# SparkFun_GNSS_NEO-M9N.net
KiCad netlist of a schematic drawn in EAGLE
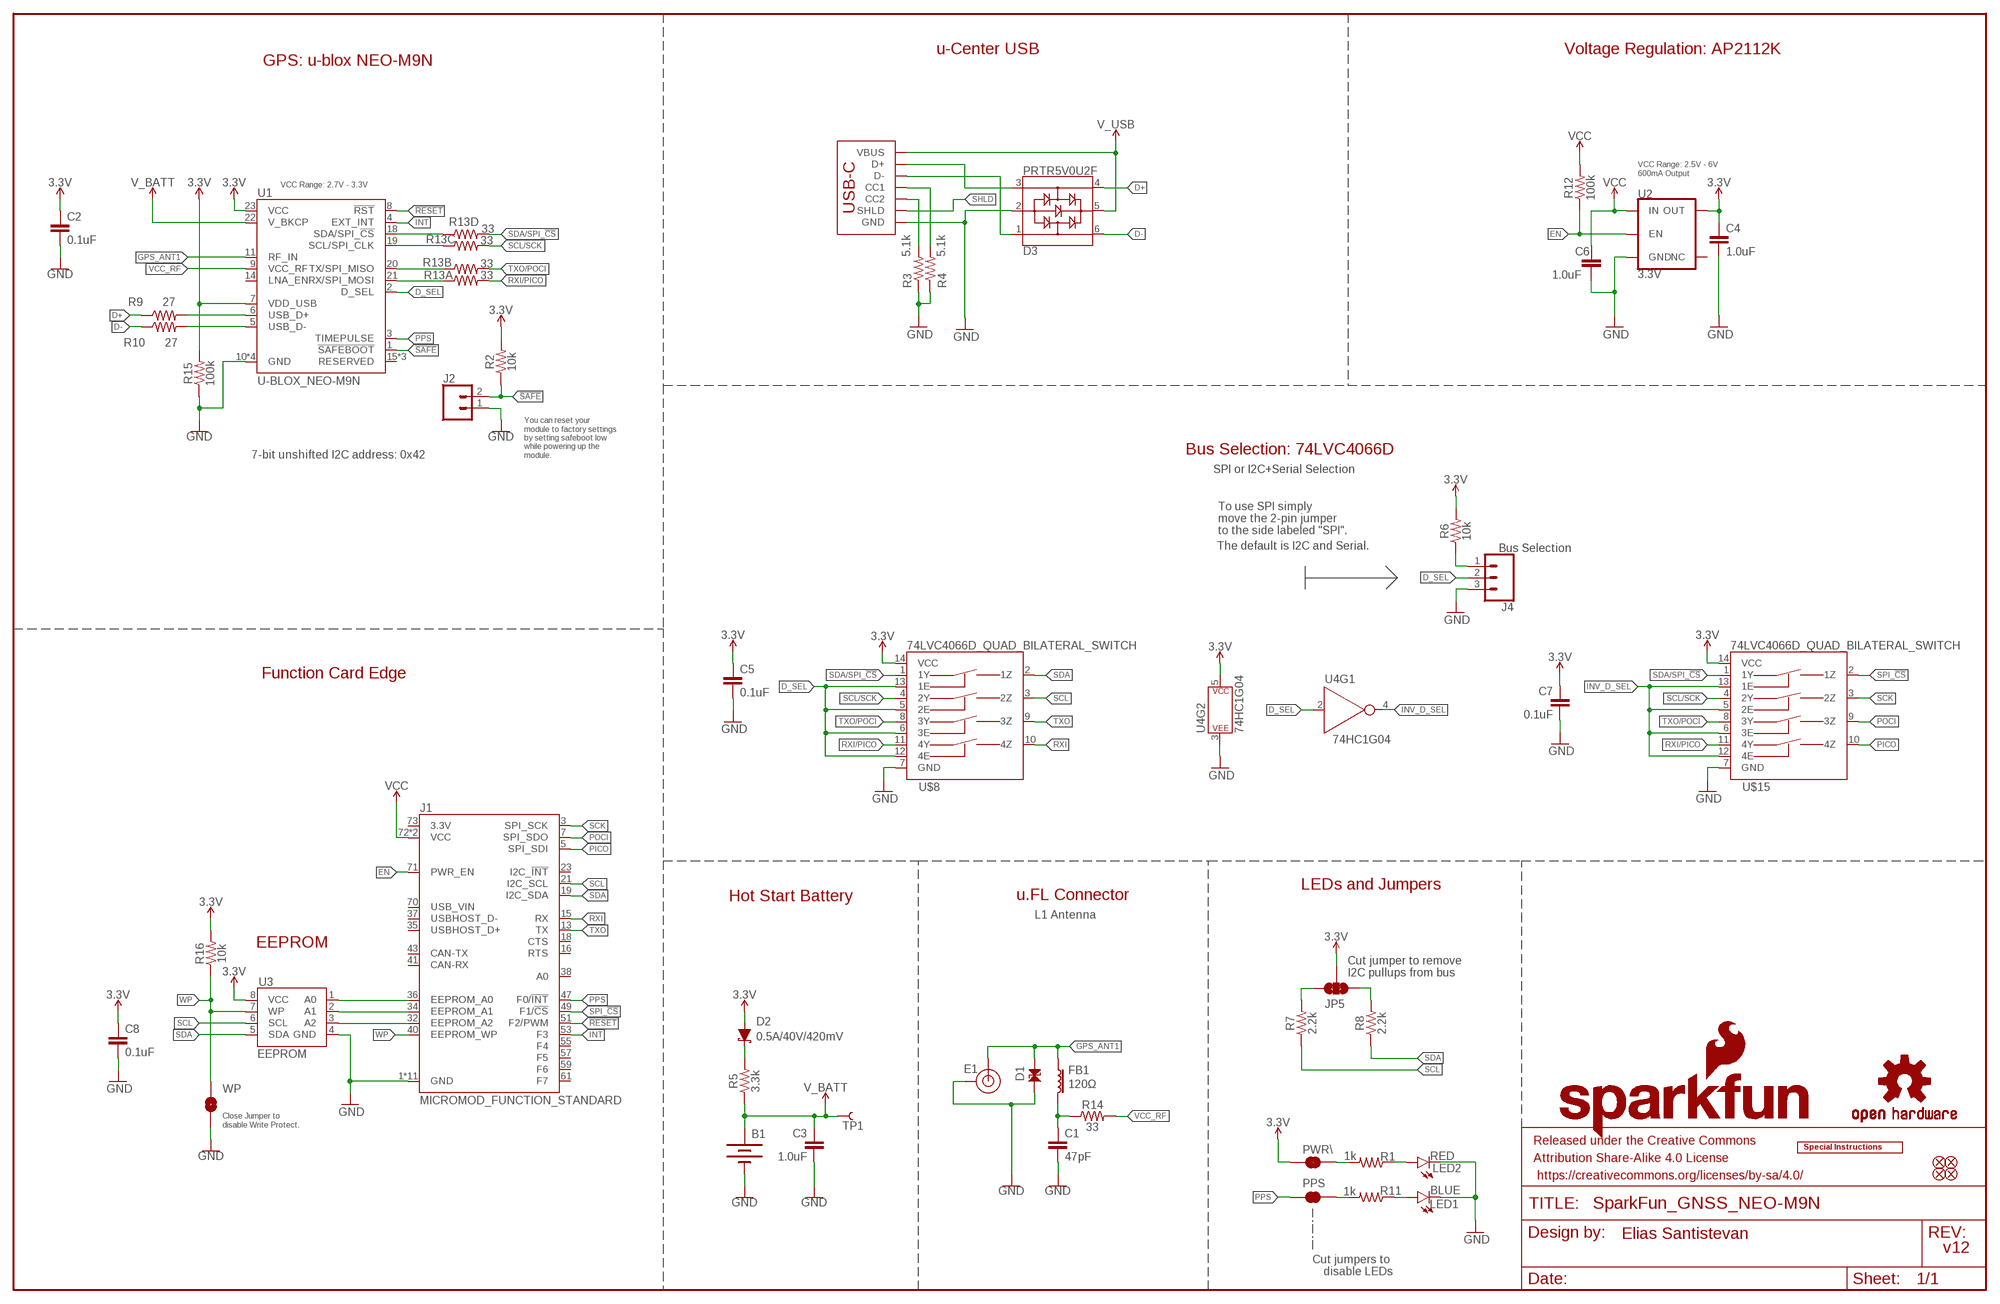
[diagram p0: schematic, sheet 1]

(export (version "E")
  (design (tool "Eeschema 10.0.6"))
  (components
    (comp (ref "B1")
      (value "6.8MM_COIN_CELL")
      (footprint "eagle-import:MS421R_IV03E")
      (libsource (lib "eagle-import") (part "RELOWABLE_BATTERY_MS421R"))
    )
    (comp (ref "C1")
      (value "47pF")
      (footprint "eagle-import:0402")
      (libsource (lib "eagle-import") (part "47PF-0402-25V-5%-X7R"))
    )
    (comp (ref "C2")
      (value "0.1uF")
      (footprint "eagle-import:0402-TIGHT")
      (libsource (lib "eagle-import") (part "0.1UF-0402T-16V-10%"))
    )
    (comp (ref "C3")
      (value "1.0uF")
      (footprint "eagle-import:0603")
      (libsource (lib "eagle-import") (part "1.0UF-0603-16V-10%"))
    )
    (comp (ref "C4")
      (value "1.0uF")
      (footprint "eagle-import:0603")
      (libsource (lib "eagle-import") (part "1.0UF-0603-16V-10%"))
    )
    (comp (ref "C5")
      (value "0.1uF")
      (footprint "eagle-import:0603")
      (libsource (lib "eagle-import") (part "0.1UF-0603-25V-(+80/-20%)"))
    )
    (comp (ref "C6")
      (value "1.0uF")
      (footprint "eagle-import:0603")
      (libsource (lib "eagle-import") (part "1.0UF-0603-16V-10%"))
    )
    (comp (ref "C7")
      (value "0.1uF")
      (footprint "eagle-import:0603")
      (libsource (lib "eagle-import") (part "0.1UF-0603-25V-(+80/-20%)"))
    )
    (comp (ref "C8")
      (value "0.1uF")
      (footprint "eagle-import:0603")
      (libsource (lib "eagle-import") (part "0.1UF-0603-25V-(+80/-20%)"))
    )
    (comp (ref "D1")
      (value "PESD0402-0402T")
      (footprint "eagle-import:0402-TIGHT")
      (libsource (lib "eagle-import") (part "PESD0402-0402T"))
    )
    (comp (ref "D2")
      (value "0.5A/40V/420mV")
      (footprint "eagle-import:SOD-323")
      (libsource (lib "eagle-import") (part "DIODE-SCHOTTKY-PMEG4005EJ"))
    )
    (comp (ref "D3")
      (value "PRTR5V0U2F")
      (footprint "eagle-import:SOT886")
      (libsource (lib "eagle-import") (part "PRTR5V0U2F"))
    )
    (comp (ref "E1")
      (value "U.FL")
      (footprint "eagle-import:U.FL")
      (libsource (lib "eagle-import") (part "U.FL2PIN"))
    )
    (comp (ref "FB1")
      (value "120Ω")
      (footprint "eagle-import:0402")
      (fields (field (name "MFG_PART") "BLM15HB121SN1D"))
      (libsource (lib "eagle-import") (part "FERRITE_BEAD-120_OHM-0402"))
    )
    (comp (ref "FD1")
      (value "FIDUCIAL1X2")
      (footprint "eagle-import:FIDUCIAL-1X2")
      (libsource (lib "eagle-import") (part "FIDUCIAL1X2"))
    )
    (comp (ref "FD2")
      (value "FIDUCIAL1X2")
      (footprint "eagle-import:FIDUCIAL-1X2")
      (libsource (lib "eagle-import") (part "FIDUCIAL1X2"))
    )
    (comp (ref "FD3")
      (value "FIDUCIAL1X2")
      (footprint "eagle-import:FIDUCIAL-1X2")
      (libsource (lib "eagle-import") (part "FIDUCIAL1X2"))
    )
    (comp (ref "FD4")
      (value "FIDUCIAL1X2")
      (footprint "eagle-import:FIDUCIAL-1X2")
      (libsource (lib "eagle-import") (part "FIDUCIAL1X2"))
    )
    (comp (ref "FRAME2")
      (value "FRAME-LEDGER")
      (footprint "eagle-import:CREATIVE_COMMONS")
      (libsource (lib "eagle-import") (part "FRAME-LEDGER"))
    )
    (comp (ref "J1")
      (value "MICROMOD_FUNCTION_STANDARD")
      (footprint "eagle-import:M.2-CARD-E-22_FUNCTION_STANDARD")
      (libsource (lib "eagle-import") (part "MICROMOD_FUNCTION_STANDARD"))
    )
    (comp (ref "J2")
      (value "CONN_02")
      (footprint "eagle-import:1X02")
      (libsource (lib "eagle-import") (part "CONN_02"))
    )
    (comp (ref "J3")
      (value "USB_C_2-LAYER_PADS")
      (footprint "eagle-import:USB-C-16P-2LAYER-PADS")
      (libsource (lib "eagle-import") (part "USB_C_2-LAYER_PADS"))
    )
    (comp (ref "J4")
      (value "Bus Selection")
      (footprint "eagle-import:1X03_LOCK")
      (libsource (lib "eagle-import") (part "CONN_03LOCK"))
    )
    (comp (ref "JP5")
      (value "JUMPER-SMT_3_2-NC_TRACE_SILK")
      (footprint "eagle-import:SMT-JUMPER_3_2-NC_TRACE_SILK")
      (libsource (lib "eagle-import") (part "JUMPER-SMT_3_2-NC_TRACE_SILK"))
    )
    (comp (ref "LED1")
      (value "BLUE")
      (footprint "eagle-import:LED-0603")
      (libsource (lib "eagle-import") (part "LED-BLUE0603"))
    )
    (comp (ref "LED2")
      (value "RED")
      (footprint "eagle-import:LED-0603")
      (libsource (lib "eagle-import") (part "LED-RED0603"))
    )
    (comp (ref "LOGO1")
      (value "SPECIAL_INSTRUCTIONS-ORDERING")
      (footprint "eagle-import:ORDERING_INSTRUCTIONS")
      (libsource (lib "eagle-import") (part "SPECIAL_INSTRUCTIONS-ORDERING"))
    )
    (comp (ref "LOGO2")
      (value "SFE_LOGO_NAME_FLAME.2_INCH")
      (footprint "eagle-import:SFE_LOGO_NAME_FLAME_.2")
      (libsource (lib "eagle-import") (part "SFE_LOGO_NAME_FLAME.2_INCH"))
    )
    (comp (ref "LOGO3")
      (value "OSHW-LOGOS")
      (footprint "eagle-import:OSHW-LOGO-S")
      (libsource (lib "eagle-import") (part "OSHW-LOGOS"))
    )
    (comp (ref "PPS")
      (value "JUMPER-SMT_2_NC_TRACE_SILK")
      (footprint "eagle-import:SMT-JUMPER_2_NC_TRACE_SILK")
      (libsource (lib "eagle-import") (part "JUMPER-SMT_2_NC_TRACE_SILK"))
    )
    (comp (ref "PWR\\")
      (value "JUMPER-SMT_2_NC_TRACE_SILK")
      (footprint "eagle-import:SMT-JUMPER_2_NC_TRACE_SILK")
      (libsource (lib "eagle-import") (part "JUMPER-SMT_2_NC_TRACE_SILK"))
    )
    (comp (ref "R1")
      (value "1k")
      (footprint "eagle-import:0603")
      (libsource (lib "eagle-import") (part "1KOHM-0603-1/10W-1%"))
    )
    (comp (ref "R2")
      (value "10k")
      (footprint "eagle-import:0603")
      (libsource (lib "eagle-import") (part "10KOHM-0603-1/10W-1%"))
    )
    (comp (ref "R3")
      (value "5.1k")
      (footprint "eagle-import:0603")
      (libsource (lib "eagle-import") (part "5.1KOHM5.1KOHM-0603-1/10W-1%"))
    )
    (comp (ref "R4")
      (value "5.1k")
      (footprint "eagle-import:0603")
      (libsource (lib "eagle-import") (part "5.1KOHM5.1KOHM-0603-1/10W-1%"))
    )
    (comp (ref "R5")
      (value "3.3k")
      (footprint "eagle-import:0603")
      (libsource (lib "eagle-import") (part "3.3KOHM-0603-1/10W-1%"))
    )
    (comp (ref "R6")
      (value "10k")
      (footprint "eagle-import:0603")
      (libsource (lib "eagle-import") (part "10KOHM-0603-1/10W-1%"))
    )
    (comp (ref "R7")
      (value "2.2k")
      (footprint "eagle-import:0603")
      (libsource (lib "eagle-import") (part "2.2KOHM-0603-1/10W-1%"))
    )
    (comp (ref "R8")
      (value "2.2k")
      (footprint "eagle-import:0603")
      (libsource (lib "eagle-import") (part "2.2KOHM-0603-1/10W-1%"))
    )
    (comp (ref "R9")
      (value "27")
      (footprint "eagle-import:0603")
      (libsource (lib "eagle-import") (part "27OHM-0603-1/10W-1%"))
    )
    (comp (ref "R10")
      (value "27")
      (footprint "eagle-import:0603")
      (libsource (lib "eagle-import") (part "27OHM-0603-1/10W-1%"))
    )
    (comp (ref "R11")
      (value "1k")
      (footprint "eagle-import:0603")
      (libsource (lib "eagle-import") (part "1KOHM-0603-1/10W-1%"))
    )
    (comp (ref "R12")
      (value "100k")
      (footprint "eagle-import:0603")
      (libsource (lib "eagle-import") (part "100KOHM-0603-1/10W-1%"))
    )
    (comp (ref "R13")
      (value "33")
      (footprint "eagle-import:1206_RA")
      (libsource (lib "eagle-import") (part "33OHM_RA-1206-1/16W-5%"))
    )
    (comp (ref "R14")
      (value "33")
      (footprint "eagle-import:0402")
      (libsource (lib "eagle-import") (part "33OHM-0402-1/10W-1%"))
    )
    (comp (ref "R15")
      (value "100k")
      (footprint "eagle-import:0603")
      (libsource (lib "eagle-import") (part "100KOHM-0603-1/10W-1%"))
    )
    (comp (ref "R16")
      (value "10k")
      (footprint "eagle-import:0603")
      (libsource (lib "eagle-import") (part "10KOHM-0603-1/10W-1%"))
    )
    (comp (ref "TP1")
      (value "TEST-POINT3X4")
      (footprint "eagle-import:PAD.03X.04")
      (libsource (lib "eagle-import") (part "TEST-POINT3X4"))
    )
    (comp (ref "U$8")
      (value "74LVC4066D_QUAD_BILATERAL_SWITCH")
      (footprint "eagle-import:SO14")
      (libsource (lib "eagle-import") (part "74LVC4066D_QUAD_BILATERAL_SWITCH"))
    )
    (comp (ref "U$15")
      (value "74LVC4066D_QUAD_BILATERAL_SWITCH")
      (footprint "eagle-import:SO14")
      (libsource (lib "eagle-import") (part "74LVC4066D_QUAD_BILATERAL_SWITCH"))
    )
    (comp (ref "U1")
      (value "U-BLOX_NEO-M9N")
      (footprint "eagle-import:NEO-M9N_M8T_M8U_D9S")
      (libsource (lib "eagle-import") (part "U-BLOX_NEO-M9N"))
    )
    (comp (ref "U2")
      (value "3.3V")
      (footprint "eagle-import:SOT23-5")
      (libsource (lib "eagle-import") (part "V_REG_AP2112K-3.3V"))
    )
    (comp (ref "U3")
      (value "EEPROM")
      (footprint "eagle-import:SO08")
      (libsource (lib "eagle-import") (part "EEPROM-I2C512K"))
    )
    (comp (ref "U4")
      (value "74HC1G04")
      (footprint "eagle-import:SOT353")
      (libsource (lib "eagle-import") (part "741G04HC"))
    )
    (comp (ref "WP")
      (value "JUMPER-SMT_2_NO_SILK")
      (footprint "eagle-import:SMT-JUMPER_2_NO_SILK")
      (libsource (lib "eagle-import") (part "JUMPER-SMT_2_NO_SILK"))
    )
  )
  (nets
    (net (code "1") (name "/SDA{slash}SPI_~{CS}") (class "Default")
      (node (ref "R13") (pin "P5") (pinfunction "2_P5") (pintype "passive"))
      (node (ref "U$15") (pin "1") (pinfunction "1Y_1") (pintype "bidirectional"))
      (node (ref "U$8") (pin "1") (pinfunction "1Y_1") (pintype "bidirectional"))
    )
    (net (code "2") (name "/SPI_~{CS}") (class "Default")
      (node (ref "J1") (pin "49") (pinfunction "F1/~{CS}_49") (pintype "bidirectional"))
      (node (ref "U$15") (pin "2") (pinfunction "1Z_2") (pintype "bidirectional"))
    )
    (net (code "3") (name "/~{RESET}") (class "Default")
      (node (ref "J1") (pin "51") (pinfunction "F2/PWM_51") (pintype "bidirectional"))
      (node (ref "U1") (pin "8") (pinfunction "~{RST}_8") (pintype "bidirectional"))
    )
    (net (code "4") (name "/~{SAFE}") (class "Default")
      (node (ref "J2") (pin "2") (pinfunction "2_2") (pintype "passive"))
      (node (ref "R2") (pin "1") (pinfunction "1_1") (pintype "passive"))
      (node (ref "U1") (pin "1") (pinfunction "~{SAFEBOOT}_1") (pintype "bidirectional"))
    )
    (net (code "5") (name "3.3V") (class "Default")
      (node (ref "C2") (pin "1") (pinfunction "1_1") (pintype "passive"))
      (node (ref "C4") (pin "1") (pinfunction "1_1") (pintype "passive"))
      (node (ref "C5") (pin "1") (pinfunction "1_1") (pintype "passive"))
      (node (ref "C7") (pin "1") (pinfunction "1_1") (pintype "passive"))
      (node (ref "C8") (pin "1") (pinfunction "1_1") (pintype "passive"))
      (node (ref "D2") (pin "A") (pinfunction "A_A") (pintype "passive"))
      (node (ref "JP5") (pin "2") (pinfunction "2_2") (pintype "passive"))
      (node (ref "PWR\\") (pin "2") (pinfunction "2_2") (pintype "passive"))
      (node (ref "R15") (pin "2") (pinfunction "2_2") (pintype "passive"))
      (node (ref "R16") (pin "2") (pinfunction "2_2") (pintype "passive"))
      (node (ref "R2") (pin "2") (pinfunction "2_2") (pintype "passive"))
      (node (ref "R6") (pin "2") (pinfunction "2_2") (pintype "passive"))
      (node (ref "U$15") (pin "14") (pinfunction "VCC_14") (pintype "bidirectional"))
      (node (ref "U$8") (pin "14") (pinfunction "VCC_14") (pintype "bidirectional"))
      (node (ref "U1") (pin "23") (pinfunction "VCC_23") (pintype "bidirectional"))
      (node (ref "U1") (pin "7") (pinfunction "VDD_USB_7") (pintype "bidirectional"))
      (node (ref "U2") (pin "5") (pinfunction "OUT_5") (pintype "passive"))
      (node (ref "U3") (pin "8") (pinfunction "VCC_8") (pintype "power_in"))
      (node (ref "U4") (pin "5") (pinfunction "P$V+_5") (pintype "bidirectional"))
    )
    (net (code "6") (name "D+") (class "Default")
      (node (ref "D3") (pin "4") (pinfunction "4_4") (pintype "bidirectional"))
      (node (ref "R9") (pin "1") (pinfunction "1_1") (pintype "passive"))
    )
    (net (code "7") (name "D-") (class "Default")
      (node (ref "D3") (pin "6") (pinfunction "6_6") (pintype "bidirectional"))
      (node (ref "R10") (pin "1") (pinfunction "1_1") (pintype "passive"))
    )
    (net (code "8") (name "D_SEL") (class "Default")
      (node (ref "J4") (pin "2") (pinfunction "2_2") (pintype "passive"))
      (node (ref "U$8") (pin "12") (pinfunction "4E_12") (pintype "bidirectional"))
      (node (ref "U$8") (pin "13") (pinfunction "1E_13") (pintype "bidirectional"))
      (node (ref "U$8") (pin "5") (pinfunction "2E_5") (pintype "bidirectional"))
      (node (ref "U$8") (pin "6") (pinfunction "3E_6") (pintype "bidirectional"))
      (node (ref "U1") (pin "2") (pinfunction "D_SEL_2") (pintype "bidirectional"))
      (node (ref "U4") (pin "2") (pinfunction "A_2") (pintype "bidirectional"))
    )
    (net (code "9") (name "EN") (class "Default")
      (node (ref "J1") (pin "71") (pinfunction "PWR_EN_71") (pintype "bidirectional"))
      (node (ref "R12") (pin "1") (pinfunction "1_1") (pintype "passive"))
      (node (ref "U2") (pin "3") (pinfunction "EN_3") (pintype "input"))
    )
    (net (code "10") (name "GND") (class "Default")
      (node (ref "B1") (pin "-") (pinfunction "-_-") (pintype "power_in"))
      (node (ref "C1") (pin "2") (pinfunction "2_2") (pintype "passive"))
      (node (ref "C2") (pin "2") (pinfunction "2_2") (pintype "passive"))
      (node (ref "C3") (pin "2") (pinfunction "2_2") (pintype "passive"))
      (node (ref "C4") (pin "2") (pinfunction "2_2") (pintype "passive"))
      (node (ref "C5") (pin "2") (pinfunction "2_2") (pintype "passive"))
      (node (ref "C6") (pin "2") (pinfunction "2_2") (pintype "passive"))
      (node (ref "C7") (pin "2") (pinfunction "2_2") (pintype "passive"))
      (node (ref "C8") (pin "2") (pinfunction "2_2") (pintype "passive"))
      (node (ref "D1") (pin "1") (pinfunction "1_1") (pintype "bidirectional"))
      (node (ref "D3") (pin "2") (pinfunction "2_2") (pintype "power_in"))
      (node (ref "E1") (pin "1") (pinfunction "GND_1") (pintype "bidirectional"))
      (node (ref "E1") (pin "2") (pinfunction "GND_2") (pintype "bidirectional"))
      (node (ref "J1") (pin "1") (pinfunction "GND_1") (pintype "bidirectional"))
      (node (ref "J1") (pin "33") (pinfunction "GND_33") (pintype "bidirectional"))
      (node (ref "J1") (pin "39") (pinfunction "GND_39") (pintype "bidirectional"))
      (node (ref "J1") (pin "45") (pinfunction "GND_45") (pintype "bidirectional"))
      (node (ref "J1") (pin "75") (pinfunction "GND_75") (pintype "bidirectional"))
      (node (ref "J1") (pin "GND1") (pinfunction "GND_GND1") (pintype "bidirectional"))
      (node (ref "J1") (pin "GND2") (pinfunction "GND_GND2") (pintype "bidirectional"))
      (node (ref "J1") (pin "GND3") (pinfunction "GND_GND3") (pintype "bidirectional"))
      (node (ref "J1") (pin "GND4") (pinfunction "GND_GND4") (pintype "bidirectional"))
      (node (ref "J1") (pin "GND5") (pinfunction "GND_GND5") (pintype "bidirectional"))
      (node (ref "J1") (pin "GND6") (pinfunction "GND_GND6") (pintype "bidirectional"))
      (node (ref "J2") (pin "1") (pinfunction "1_1") (pintype "passive"))
      (node (ref "J3") (pin "GND") (pinfunction "GND_GND") (pintype "bidirectional"))
      (node (ref "J3") (pin "GND2") (pinfunction "GND_GND2") (pintype "bidirectional"))
      (node (ref "J4") (pin "3") (pinfunction "3_3") (pintype "passive"))
      (node (ref "LED1") (pin "C") (pinfunction "C_C") (pintype "passive"))
      (node (ref "LED2") (pin "C") (pinfunction "C_C") (pintype "passive"))
      (node (ref "R15") (pin "1") (pinfunction "1_1") (pintype "passive"))
      (node (ref "R3") (pin "1") (pinfunction "1_1") (pintype "passive"))
      (node (ref "R4") (pin "1") (pinfunction "1_1") (pintype "passive"))
      (node (ref "U$15") (pin "7") (pinfunction "GND_7") (pintype "bidirectional"))
      (node (ref "U$8") (pin "7") (pinfunction "GND_7") (pintype "bidirectional"))
      (node (ref "U1") (pin "10") (pinfunction "GND_10") (pintype "bidirectional"))
      (node (ref "U1") (pin "12") (pinfunction "GND_12") (pintype "bidirectional"))
      (node (ref "U1") (pin "13") (pinfunction "GND_13") (pintype "bidirectional"))
      (node (ref "U1") (pin "24") (pinfunction "GND_24") (pintype "bidirectional"))
      (node (ref "U2") (pin "2") (pinfunction "GND_2") (pintype "input"))
      (node (ref "U3") (pin "4") (pinfunction "GND_4") (pintype "power_in"))
      (node (ref "U4") (pin "3") (pinfunction "P$V-_3") (pintype "bidirectional"))
      (node (ref "WP") (pin "1") (pinfunction "1_1") (pintype "passive"))
    )
    (net (code "11") (name "GPS_ANT1") (class "Default")
      (node (ref "D1") (pin "2") (pinfunction "2_2") (pintype "bidirectional"))
      (node (ref "E1") (pin "FEED") (pinfunction "SIGNAL_FEED") (pintype "bidirectional"))
      (node (ref "FB1") (pin "1") (pinfunction "1_1") (pintype "passive"))
      (node (ref "U1") (pin "11") (pinfunction "RF_IN_11") (pintype "bidirectional"))
    )
    (net (code "12") (name "INT") (class "Default")
      (node (ref "J1") (pin "53") (pinfunction "F3_53") (pintype "bidirectional"))
      (node (ref "U1") (pin "4") (pinfunction "EXT_INT_4") (pintype "bidirectional"))
    )
    (net (code "13") (name "INV_D_SEL") (class "Default")
      (node (ref "U$15") (pin "12") (pinfunction "4E_12") (pintype "bidirectional"))
      (node (ref "U$15") (pin "13") (pinfunction "1E_13") (pintype "bidirectional"))
      (node (ref "U$15") (pin "5") (pinfunction "2E_5") (pintype "bidirectional"))
      (node (ref "U$15") (pin "6") (pinfunction "3E_6") (pintype "bidirectional"))
      (node (ref "U4") (pin "4") (pinfunction "Y_4") (pintype "bidirectional"))
    )
    (net (code "14") (name "Net-(C1-Pad1)") (class "Default")
      (node (ref "C1") (pin "1") (pinfunction "1_1") (pintype "passive"))
      (node (ref "FB1") (pin "2") (pinfunction "2_2") (pintype "passive"))
      (node (ref "R14") (pin "1") (pinfunction "1_1") (pintype "passive"))
    )
    (net (code "15") (name "Net-(D2-PadC)") (class "Default")
      (node (ref "D2") (pin "C") (pinfunction "C_C") (pintype "passive"))
      (node (ref "R5") (pin "2") (pinfunction "2_2") (pintype "passive"))
    )
    (net (code "16") (name "Net-(D3-Pad1)") (class "Default")
      (node (ref "D3") (pin "1") (pinfunction "1_1") (pintype "bidirectional"))
      (node (ref "J3") (pin "A7") (pinfunction "D-_A7") (pintype "bidirectional"))
      (node (ref "J3") (pin "B7") (pinfunction "D-_B7") (pintype "bidirectional"))
    )
    (net (code "17") (name "Net-(D3-Pad3)") (class "Default")
      (node (ref "D3") (pin "3") (pinfunction "3_3") (pintype "bidirectional"))
      (node (ref "J3") (pin "A6") (pinfunction "D+_A6") (pintype "bidirectional"))
      (node (ref "J3") (pin "B6") (pinfunction "D+_B6") (pintype "bidirectional"))
    )
    (net (code "18") (name "Net-(J1-EEPROM_A0)") (class "Default")
      (node (ref "J1") (pin "36") (pinfunction "EEPROM_A0_36") (pintype "bidirectional"))
      (node (ref "U3") (pin "1") (pinfunction "A0_1") (pintype "bidirectional"))
    )
    (net (code "19") (name "Net-(J1-EEPROM_A1)") (class "Default")
      (node (ref "J1") (pin "34") (pinfunction "EEPROM_A1_34") (pintype "bidirectional"))
      (node (ref "U3") (pin "2") (pinfunction "A1_2") (pintype "bidirectional"))
    )
    (net (code "20") (name "Net-(J1-EEPROM_A2)") (class "Default")
      (node (ref "J1") (pin "32") (pinfunction "EEPROM_A2_32") (pintype "bidirectional"))
      (node (ref "U3") (pin "3") (pinfunction "A2_3") (pintype "bidirectional"))
    )
    (net (code "21") (name "Net-(J3-CC1)") (class "Default")
      (node (ref "J3") (pin "A5") (pinfunction "CC1_A5") (pintype "bidirectional"))
      (node (ref "R4") (pin "2") (pinfunction "2_2") (pintype "passive"))
    )
    (net (code "22") (name "Net-(J3-CC2)") (class "Default")
      (node (ref "J3") (pin "B5") (pinfunction "CC2_B5") (pintype "bidirectional"))
      (node (ref "R3") (pin "2") (pinfunction "2_2") (pintype "passive"))
    )
    (net (code "23") (name "Net-(J4-Pad1)") (class "Default")
      (node (ref "J4") (pin "1") (pinfunction "1_1") (pintype "passive"))
      (node (ref "R6") (pin "1") (pinfunction "1_1") (pintype "passive"))
    )
    (net (code "24") (name "Net-(JP5-Pad1)") (class "Default")
      (node (ref "JP5") (pin "1") (pinfunction "1_1") (pintype "passive"))
      (node (ref "R8") (pin "2") (pinfunction "2_2") (pintype "passive"))
    )
    (net (code "25") (name "Net-(JP5-Pad3)") (class "Default")
      (node (ref "JP5") (pin "3") (pinfunction "3_3") (pintype "passive"))
      (node (ref "R7") (pin "2") (pinfunction "2_2") (pintype "passive"))
    )
    (net (code "26") (name "Net-(LED1-PadA)") (class "Default")
      (node (ref "LED1") (pin "A") (pinfunction "A_A") (pintype "passive"))
      (node (ref "R11") (pin "1") (pinfunction "1_1") (pintype "passive"))
    )
    (net (code "27") (name "Net-(LED2-PadA)") (class "Default")
      (node (ref "LED2") (pin "A") (pinfunction "A_A") (pintype "passive"))
      (node (ref "R1") (pin "1") (pinfunction "1_1") (pintype "passive"))
    )
    (net (code "28") (name "Net-(PPS-Pad1)") (class "Default")
      (node (ref "PPS") (pin "1") (pinfunction "1_1") (pintype "passive"))
      (node (ref "R11") (pin "2") (pinfunction "2_2") (pintype "passive"))
    )
    (net (code "29") (name "Net-(PWR\\-Pad1)") (class "Default")
      (node (ref "PWR\\") (pin "1") (pinfunction "1_1") (pintype "passive"))
      (node (ref "R1") (pin "2") (pinfunction "2_2") (pintype "passive"))
    )
    (net (code "30") (name "Net-(R13A-1)") (class "Default")
      (node (ref "R13") (pin "P1") (pinfunction "1_P1") (pintype "passive"))
      (node (ref "U1") (pin "21") (pinfunction "RX/SPI_MOSI_21") (pintype "bidirectional"))
    )
    (net (code "31") (name "Net-(R13B-1)") (class "Default")
      (node (ref "R13") (pin "P2") (pinfunction "1_P2") (pintype "passive"))
      (node (ref "U1") (pin "20") (pinfunction "TX/SPI_MISO_20") (pintype "bidirectional"))
    )
    (net (code "32") (name "Net-(R13C-1)") (class "Default")
      (node (ref "R13") (pin "P3") (pinfunction "1_P3") (pintype "passive"))
      (node (ref "U1") (pin "19") (pinfunction "SCL/SPI_CLK_19") (pintype "bidirectional"))
    )
    (net (code "33") (name "Net-(R13D-1)") (class "Default")
      (node (ref "R13") (pin "P4") (pinfunction "1_P4") (pintype "passive"))
      (node (ref "U1") (pin "18") (pinfunction "SDA/SPI_~{CS}_18") (pintype "bidirectional"))
    )
    (net (code "34") (name "Net-(U1-USB_D+)") (class "Default")
      (node (ref "R9") (pin "2") (pinfunction "2_2") (pintype "passive"))
      (node (ref "U1") (pin "6") (pinfunction "USB_D+_6") (pintype "bidirectional"))
    )
    (net (code "35") (name "Net-(U1-USB_D-)") (class "Default")
      (node (ref "R10") (pin "2") (pinfunction "2_2") (pintype "passive"))
      (node (ref "U1") (pin "5") (pinfunction "USB_D-_5") (pintype "bidirectional"))
    )
    (net (code "36") (name "PICO") (class "Default")
      (node (ref "J1") (pin "5") (pinfunction "SPI_SDI_5") (pintype "bidirectional"))
      (node (ref "U$15") (pin "10") (pinfunction "4Z_10") (pintype "bidirectional"))
    )
    (net (code "37") (name "POCI") (class "Default")
      (node (ref "J1") (pin "7") (pinfunction "SPI_SDO_7") (pintype "bidirectional"))
      (node (ref "U$15") (pin "9") (pinfunction "3Z_9") (pintype "bidirectional"))
    )
    (net (code "38") (name "PPS") (class "Default")
      (node (ref "J1") (pin "47") (pinfunction "F0/~{INT}_47") (pintype "bidirectional"))
      (node (ref "PPS") (pin "2") (pinfunction "2_2") (pintype "passive"))
      (node (ref "U1") (pin "3") (pinfunction "TIMEPULSE_3") (pintype "bidirectional"))
    )
    (net (code "39") (name "RXI") (class "Default")
      (node (ref "J1") (pin "15") (pinfunction "RX_15") (pintype "bidirectional"))
      (node (ref "U$8") (pin "10") (pinfunction "4Z_10") (pintype "bidirectional"))
    )
    (net (code "40") (name "RXI{slash}PICO") (class "Default")
      (node (ref "R13") (pin "P8") (pinfunction "2_P8") (pintype "passive"))
      (node (ref "U$15") (pin "11") (pinfunction "4Y_11") (pintype "bidirectional"))
      (node (ref "U$8") (pin "11") (pinfunction "4Y_11") (pintype "bidirectional"))
    )
    (net (code "41") (name "SCK") (class "Default")
      (node (ref "J1") (pin "3") (pinfunction "SPI_SCK_3") (pintype "bidirectional"))
      (node (ref "U$15") (pin "3") (pinfunction "2Z_3") (pintype "bidirectional"))
    )
    (net (code "42") (name "SCL") (class "Default")
      (node (ref "J1") (pin "21") (pinfunction "I2C_SCL_21") (pintype "bidirectional"))
      (node (ref "R7") (pin "1") (pinfunction "1_1") (pintype "passive"))
      (node (ref "U$8") (pin "3") (pinfunction "2Z_3") (pintype "bidirectional"))
      (node (ref "U3") (pin "6") (pinfunction "SCL_6") (pintype "bidirectional"))
    )
    (net (code "43") (name "SCL{slash}SCK") (class "Default")
      (node (ref "R13") (pin "P6") (pinfunction "2_P6") (pintype "passive"))
      (node (ref "U$15") (pin "4") (pinfunction "2Y_4") (pintype "bidirectional"))
      (node (ref "U$8") (pin "4") (pinfunction "2Y_4") (pintype "bidirectional"))
    )
    (net (code "44") (name "SDA") (class "Default")
      (node (ref "J1") (pin "19") (pinfunction "I2C_SDA_19") (pintype "bidirectional"))
      (node (ref "R8") (pin "1") (pinfunction "1_1") (pintype "passive"))
      (node (ref "U$8") (pin "2") (pinfunction "1Z_2") (pintype "bidirectional"))
      (node (ref "U3") (pin "5") (pinfunction "SDA_5") (pintype "bidirectional"))
    )
    (net (code "45") (name "SHLD") (class "Default")
      (node (ref "J3") (pin "SHLD1") (pinfunction "SHLD_SHLD1") (pintype "bidirectional"))
      (node (ref "J3") (pin "SHLD2") (pinfunction "SHLD_SHLD2") (pintype "bidirectional"))
      (node (ref "J3") (pin "SHLD3") (pinfunction "SHLD_SHLD3") (pintype "bidirectional"))
      (node (ref "J3") (pin "SHLD4") (pinfunction "SHLD_SHLD4") (pintype "bidirectional"))
    )
    (net (code "46") (name "TXO") (class "Default")
      (node (ref "J1") (pin "13") (pinfunction "TX_13") (pintype "bidirectional"))
      (node (ref "U$8") (pin "9") (pinfunction "3Z_9") (pintype "bidirectional"))
    )
    (net (code "47") (name "TXO{slash}POCI") (class "Default")
      (node (ref "R13") (pin "P7") (pinfunction "2_P7") (pintype "passive"))
      (node (ref "U$15") (pin "8") (pinfunction "3Y_8") (pintype "bidirectional"))
      (node (ref "U$8") (pin "8") (pinfunction "3Y_8") (pintype "bidirectional"))
    )
    (net (code "48") (name "VCC") (class "Default")
      (node (ref "C6") (pin "1") (pinfunction "1_1") (pintype "passive"))
      (node (ref "J1") (pin "72") (pinfunction "VCC_72") (pintype "bidirectional"))
      (node (ref "J1") (pin "74") (pinfunction "VCC_74") (pintype "bidirectional"))
      (node (ref "R12") (pin "2") (pinfunction "2_2") (pintype "passive"))
      (node (ref "U2") (pin "1") (pinfunction "IN_1") (pintype "input"))
    )
    (net (code "49") (name "VCC_RF") (class "Default")
      (node (ref "R14") (pin "2") (pinfunction "2_2") (pintype "passive"))
      (node (ref "U1") (pin "9") (pinfunction "VCC_RF_9") (pintype "bidirectional"))
    )
    (net (code "50") (name "V_BATT") (class "Default")
      (node (ref "B1") (pin "+") (pinfunction "+_+") (pintype "power_in"))
      (node (ref "C3") (pin "1") (pinfunction "1_1") (pintype "passive"))
      (node (ref "R5") (pin "1") (pinfunction "1_1") (pintype "passive"))
      (node (ref "TP1") (pin "1") (pinfunction "1_1") (pintype "bidirectional"))
      (node (ref "U1") (pin "22") (pinfunction "V_BKCP_22") (pintype "bidirectional"))
    )
    (net (code "51") (name "V_USB") (class "Default")
      (node (ref "D3") (pin "5") (pinfunction "5_5") (pintype "power_in"))
      (node (ref "J3") (pin "VBUS1") (pinfunction "VBUS_VBUS1") (pintype "bidirectional"))
      (node (ref "J3") (pin "VBUS2") (pinfunction "VBUS_VBUS2") (pintype "bidirectional"))
    )
    (net (code "52") (name "WP") (class "Default")
      (node (ref "J1") (pin "40") (pinfunction "EEPROM_WP_40") (pintype "bidirectional"))
      (node (ref "R16") (pin "1") (pinfunction "1_1") (pintype "passive"))
      (node (ref "U3") (pin "7") (pinfunction "WP_7") (pintype "bidirectional"))
      (node (ref "WP") (pin "2") (pinfunction "2_2") (pintype "passive"))
    )
    (net (code "53") (name "unconnected-(J1-3.3V-Pad73)") (class "Default")
      (node (ref "J1") (pin "73") (pinfunction "3.3V_73") (pintype "bidirectional"))
    )
    (net (code "54") (name "unconnected-(J1-A0-Pad38)") (class "Default")
      (node (ref "J1") (pin "38") (pinfunction "A0_38") (pintype "bidirectional"))
    )
    (net (code "55") (name "unconnected-(J1-CAN-RX-Pad41)") (class "Default")
      (node (ref "J1") (pin "41") (pinfunction "CAN-RX_41") (pintype "bidirectional"))
    )
    (net (code "56") (name "unconnected-(J1-CAN-TX-Pad43)") (class "Default")
      (node (ref "J1") (pin "43") (pinfunction "CAN-TX_43") (pintype "bidirectional"))
    )
    (net (code "57") (name "unconnected-(J1-CTS-Pad18)") (class "Default")
      (node (ref "J1") (pin "18") (pinfunction "CTS_18") (pintype "bidirectional"))
    )
    (net (code "58") (name "unconnected-(J1-F4-Pad55)") (class "Default")
      (node (ref "J1") (pin "55") (pinfunction "F4_55") (pintype "bidirectional"))
    )
    (net (code "59") (name "unconnected-(J1-F5-Pad57)") (class "Default")
      (node (ref "J1") (pin "57") (pinfunction "F5_57") (pintype "bidirectional"))
    )
    (net (code "60") (name "unconnected-(J1-F6-Pad59)") (class "Default")
      (node (ref "J1") (pin "59") (pinfunction "F6_59") (pintype "bidirectional"))
    )
    (net (code "61") (name "unconnected-(J1-F7-Pad61)") (class "Default")
      (node (ref "J1") (pin "61") (pinfunction "F7_61") (pintype "bidirectional"))
    )
    (net (code "62") (name "unconnected-(J1-I2C_~{INT}-Pad23)") (class "Default")
      (node (ref "J1") (pin "23") (pinfunction "I2C_~{INT}_23") (pintype "bidirectional"))
    )
    (net (code "63") (name "unconnected-(J1-RTS-Pad16)") (class "Default")
      (node (ref "J1") (pin "16") (pinfunction "RTS_16") (pintype "bidirectional"))
    )
    (net (code "64") (name "unconnected-(J1-USBHOST_D+-Pad35)") (class "Default")
      (node (ref "J1") (pin "35") (pinfunction "USBHOST_D+_35") (pintype "bidirectional"))
    )
    (net (code "65") (name "unconnected-(J1-USBHOST_D--Pad37)") (class "Default")
      (node (ref "J1") (pin "37") (pinfunction "USBHOST_D-_37") (pintype "bidirectional"))
    )
    (net (code "66") (name "unconnected-(J1-USB_VIN-Pad70)") (class "Default")
      (node (ref "J1") (pin "70") (pinfunction "USB_VIN_70") (pintype "bidirectional"))
    )
    (net (code "67") (name "unconnected-(U1-LNA_EN-Pad14)") (class "Default")
      (node (ref "U1") (pin "14") (pinfunction "LNA_EN_14") (pintype "bidirectional"))
    )
    (net (code "68") (name "unconnected-(U1-RESERVED-Pad15)") (class "Default")
      (node (ref "U1") (pin "15") (pinfunction "RESERVED_15") (pintype "no_connect"))
    )
    (net (code "69") (name "unconnected-(U1-RESERVED-Pad16)") (class "Default")
      (node (ref "U1") (pin "16") (pinfunction "RESERVED_16") (pintype "no_connect"))
    )
    (net (code "70") (name "unconnected-(U1-RESERVED-Pad17)") (class "Default")
      (node (ref "U1") (pin "17") (pinfunction "RESERVED_17") (pintype "no_connect"))
    )
    (net (code "71") (name "unconnected-(U2-NC-Pad4)") (class "Default")
      (node (ref "U2") (pin "4") (pinfunction "NC_4") (pintype "no_connect"))
    )
  )
)
